# CubeSat_Power_Supply_Mk_3.net
KiCad netlist of a schematic drawn in EAGLE
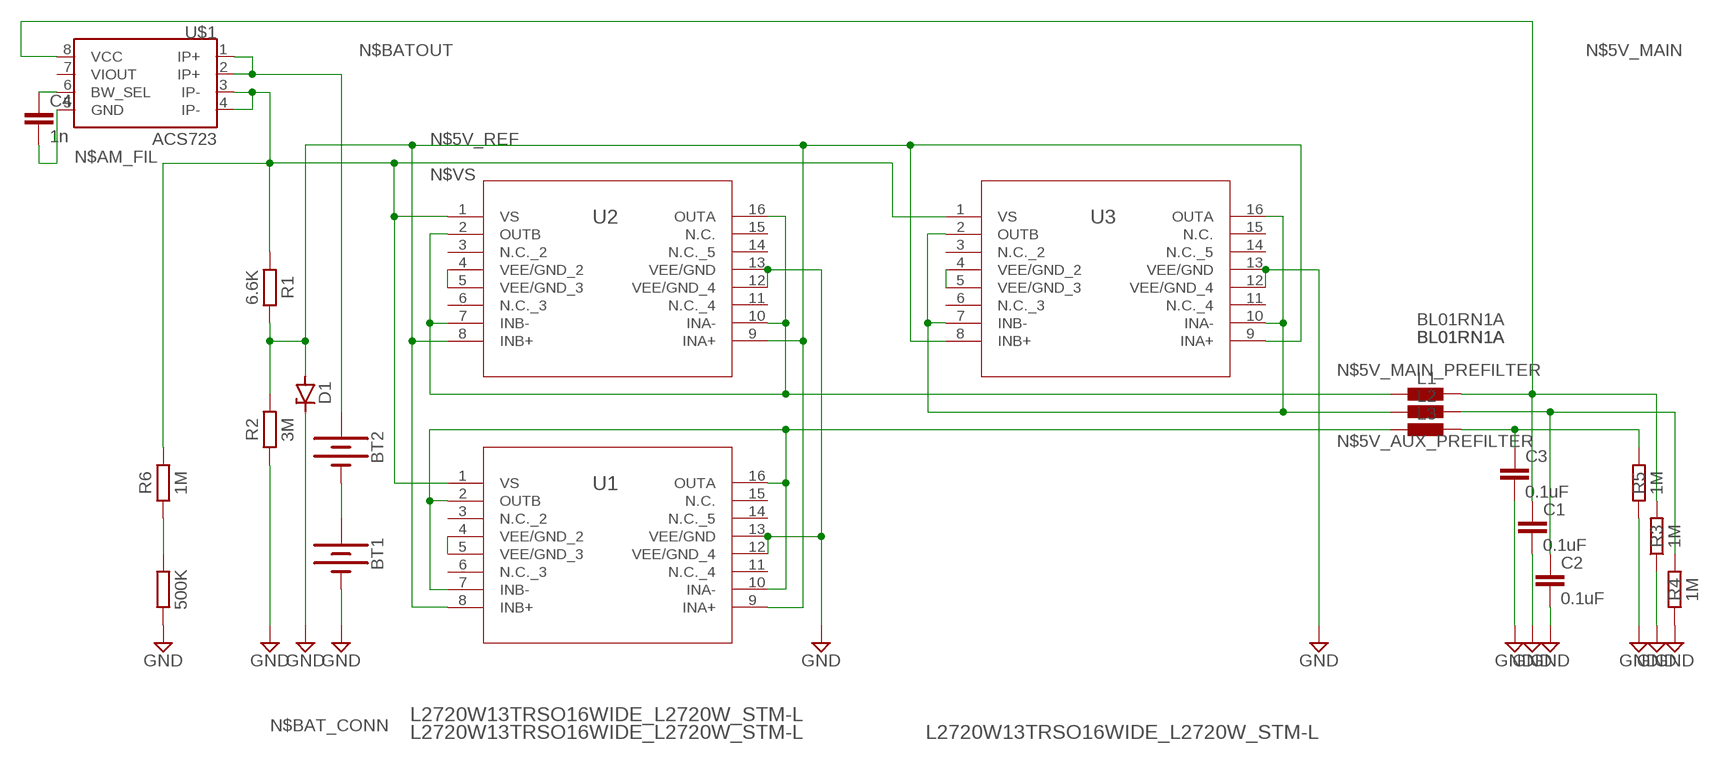
[diagram p0: schematic, sheet 1]

(export (version "E")
  (design (tool "Eeschema 10.0.6"))
  (components
    (comp (ref "BT1")
      (value "BATTERY-18650")
      (footprint "eagle-import:BATTERY_18650-HOLDER")
      (libsource (lib "eagle-import") (part "BATTERY-18650"))
    )
    (comp (ref "BT2")
      (value "BATTERY-18650")
      (footprint "eagle-import:BATTERY_18650-HOLDER")
      (libsource (lib "eagle-import") (part "BATTERY-18650"))
    )
    (comp (ref "C1")
      (value "0.1uF")
      (footprint "eagle-import:CAP-PTH-SMALL-KIT")
      (libsource (lib "eagle-import") (part "0.1UF-KIT-EZ-50V-20%"))
    )
    (comp (ref "C2")
      (value "0.1uF")
      (footprint "eagle-import:CAP-PTH-SMALL-KIT")
      (libsource (lib "eagle-import") (part "0.1UF-KIT-EZ-50V-20%"))
    )
    (comp (ref "C3")
      (value "0.1uF")
      (footprint "eagle-import:CAP-PTH-SMALL-KIT")
      (libsource (lib "eagle-import") (part "0.1UF-KIT-EZ-50V-20%"))
    )
    (comp (ref "C4")
      (value "1n")
      (footprint "eagle-import:CAP-PTH-SMALL-KIT")
      (libsource (lib "eagle-import") (part "0.1UF-KIT-EZ-50V-20%"))
    )
    (comp (ref "D1")
      (value "ZENER-DIODESOT23")
      (footprint "eagle-import:SOT23")
      (libsource (lib "eagle-import") (part "ZENER-DIODESOT23"))
    )
    (comp (ref "L1")
      (value "BL01RN1A")
      (footprint "eagle-import:BL01RN1A")
      (libsource (lib "eagle-import") (part "BL01RN1A"))
    )
    (comp (ref "L2")
      (value "BL01RN1A")
      (footprint "eagle-import:BL01RN1A")
      (libsource (lib "eagle-import") (part "BL01RN1A"))
    )
    (comp (ref "L3")
      (value "BL01RN1A")
      (footprint "eagle-import:BL01RN1A")
      (libsource (lib "eagle-import") (part "BL01RN1A"))
    )
    (comp (ref "R1")
      (value "6.6K")
      (footprint "eagle-import:RESAD724W46L381D178B")
      (libsource (lib "eagle-import") (part "RAXIAL-7.2MM-PITCH_"))
    )
    (comp (ref "R2")
      (value "3M")
      (footprint "eagle-import:RESAD724W46L381D178B")
      (libsource (lib "eagle-import") (part "RAXIAL-7.2MM-PITCH_"))
    )
    (comp (ref "R3")
      (value "1M")
      (footprint "eagle-import:RESAD724W46L381D178B")
      (libsource (lib "eagle-import") (part "RAXIAL-7.2MM-PITCH_"))
    )
    (comp (ref "R4")
      (value "1M")
      (footprint "eagle-import:RESAD724W46L381D178B")
      (libsource (lib "eagle-import") (part "RAXIAL-7.2MM-PITCH_"))
    )
    (comp (ref "R5")
      (value "1M")
      (footprint "eagle-import:RESAD724W46L381D178B")
      (libsource (lib "eagle-import") (part "RAXIAL-7.2MM-PITCH_"))
    )
    (comp (ref "R6")
      (value "1M")
      (footprint "eagle-import:RESAD724W46L381D178B")
      (libsource (lib "eagle-import") (part "RAXIAL-7.2MM-PITCH_"))
    )
    (comp (ref "R7")
      (value "500K")
      (footprint "eagle-import:RESAD724W46L381D178B")
      (libsource (lib "eagle-import") (part "RAXIAL-7.2MM-PITCH_"))
    )
    (comp (ref "U$1")
      (value "ACS723")
      (footprint "eagle-import:SO08")
      (fields (field (name "PART_#") "ACS723ACS723LLCTR-05AB-T2"))
      (libsource (lib "eagle-import") (part "ACS723"))
    )
    (comp (ref "U1")
      (value "L2720W13TRSO16WIDE_L2720W_STM-L")
      (footprint "eagle-import:SO16WIDE_L2720W_STM-L")
      (fields
        (field (name "MANUFACTURER_PART_NUMBER") "L2720W13TR")
        (field (name "COPYRIGHT") "Copyright (C) 2024 Ultra Librarian. All rights reserved.")
      )
      (libsource (lib "eagle-import") (part "L2720W13TRSO16WIDE_L2720W_STM-L"))
    )
    (comp (ref "U2")
      (value "L2720W13TRSO16WIDE_L2720W_STM-L")
      (footprint "eagle-import:SO16WIDE_L2720W_STM-L")
      (fields
        (field (name "MANUFACTURER_PART_NUMBER") "L2720W13TR")
        (field (name "COPYRIGHT") "Copyright (C) 2024 Ultra Librarian. All rights reserved.")
      )
      (libsource (lib "eagle-import") (part "L2720W13TRSO16WIDE_L2720W_STM-L"))
    )
    (comp (ref "U3")
      (value "L2720W13TRSO16WIDE_L2720W_STM-L")
      (footprint "eagle-import:SO16WIDE_L2720W_STM-L")
      (fields
        (field (name "MANUFACTURER_PART_NUMBER") "L2720W13TR")
        (field (name "COPYRIGHT") "Copyright (C) 2024 Ultra Librarian. All rights reserved.")
      )
      (libsource (lib "eagle-import") (part "L2720W13TRSO16WIDE_L2720W_STM-L"))
    )
  )
  (nets
    (net (code "1") (name "/N$5V_AUX_PREFILTER") (class "Default")
      (node (ref "L2") (pin "1") (pinfunction "1_1") (pintype "passive"))
      (node (ref "U3") (pin "10") (pinfunction "INA-_10") (pintype "input"))
      (node (ref "U3") (pin "16") (pinfunction "OUTA_16") (pintype "output"))
      (node (ref "U3") (pin "2") (pinfunction "OUTB_2") (pintype "output"))
      (node (ref "U3") (pin "7") (pinfunction "INB-_7") (pintype "input"))
    )
    (net (code "2") (name "/N$5V_MAIN") (class "Default")
      (node (ref "C1") (pin "1") (pinfunction "1_1") (pintype "passive"))
      (node (ref "L1") (pin "2") (pinfunction "2_2") (pintype "passive"))
      (node (ref "R3") (pin "2") (pinfunction "2_2") (pintype "passive"))
      (node (ref "U$1") (pin "8") (pinfunction "VCC_8") (pintype "bidirectional"))
    )
    (net (code "3") (name "/N$5V_MAIN_PREFILTER") (class "Default")
      (node (ref "L1") (pin "1") (pinfunction "1_1") (pintype "passive"))
      (node (ref "U2") (pin "10") (pinfunction "INA-_10") (pintype "input"))
      (node (ref "U2") (pin "16") (pinfunction "OUTA_16") (pintype "output"))
      (node (ref "U2") (pin "2") (pinfunction "OUTB_2") (pintype "output"))
      (node (ref "U2") (pin "7") (pinfunction "INB-_7") (pintype "input"))
    )
    (net (code "4") (name "/N$5V_REF") (class "Default")
      (node (ref "D1") (pin "1") (pinfunction "A_1") (pintype "passive"))
      (node (ref "R1") (pin "2") (pinfunction "2_2") (pintype "passive"))
      (node (ref "R2") (pin "2") (pinfunction "2_2") (pintype "passive"))
      (node (ref "U1") (pin "8") (pinfunction "INB+_8") (pintype "input"))
      (node (ref "U1") (pin "9") (pinfunction "INA+_9") (pintype "input"))
      (node (ref "U2") (pin "8") (pinfunction "INB+_8") (pintype "input"))
      (node (ref "U2") (pin "9") (pinfunction "INA+_9") (pintype "input"))
      (node (ref "U3") (pin "8") (pinfunction "INB+_8") (pintype "input"))
      (node (ref "U3") (pin "9") (pinfunction "INA+_9") (pintype "input"))
    )
    (net (code "5") (name "/N$AM_FIL") (class "Default")
      (node (ref "C4") (pin "1") (pinfunction "1_1") (pintype "passive"))
      (node (ref "U$1") (pin "6") (pinfunction "BW_SEL_6") (pintype "bidirectional"))
    )
    (net (code "6") (name "/N$BATOUT") (class "Default")
      (node (ref "BT2") (pin "PWR@1") (pinfunction "+_PWR@1") (pintype "power_in"))
      (node (ref "U$1") (pin "1") (pinfunction "IP+_1") (pintype "input"))
      (node (ref "U$1") (pin "2") (pinfunction "IP+_2") (pintype "input"))
    )
    (net (code "7") (name "/N$BAT_CONN") (class "Default")
      (node (ref "BT1") (pin "PWR@1") (pinfunction "+_PWR@1") (pintype "power_in"))
      (node (ref "BT2") (pin "GND@1") (pinfunction "-_GND@1") (pintype "power_in"))
    )
    (net (code "8") (name "/N$VS") (class "Default")
      (node (ref "R1") (pin "1") (pinfunction "1_1") (pintype "passive"))
      (node (ref "R6") (pin "2") (pinfunction "2_2") (pintype "passive"))
      (node (ref "U$1") (pin "3") (pinfunction "IP-_3") (pintype "bidirectional"))
      (node (ref "U$1") (pin "4") (pinfunction "IP-_4") (pintype "bidirectional"))
      (node (ref "U1") (pin "1") (pinfunction "VS_1") (pintype "power_in"))
      (node (ref "U2") (pin "1") (pinfunction "VS_1") (pintype "power_in"))
      (node (ref "U3") (pin "1") (pinfunction "VS_1") (pintype "power_in"))
    )
    (net (code "9") (name "GND") (class "Default")
      (node (ref "BT1") (pin "GND@1") (pinfunction "-_GND@1") (pintype "power_in"))
      (node (ref "C1") (pin "2") (pinfunction "2_2") (pintype "passive"))
      (node (ref "C2") (pin "2") (pinfunction "2_2") (pintype "passive"))
      (node (ref "C3") (pin "2") (pinfunction "2_2") (pintype "passive"))
      (node (ref "D1") (pin "3") (pinfunction "C_3") (pintype "passive"))
      (node (ref "R2") (pin "1") (pinfunction "1_1") (pintype "passive"))
      (node (ref "R3") (pin "1") (pinfunction "1_1") (pintype "passive"))
      (node (ref "R4") (pin "1") (pinfunction "1_1") (pintype "passive"))
      (node (ref "R5") (pin "1") (pinfunction "1_1") (pintype "passive"))
      (node (ref "R7") (pin "1") (pinfunction "1_1") (pintype "passive"))
      (node (ref "U1") (pin "12") (pinfunction "VEE/GND_4_12") (pintype "power_in"))
      (node (ref "U1") (pin "13") (pinfunction "VEE/GND_13") (pintype "power_in"))
      (node (ref "U2") (pin "12") (pinfunction "VEE/GND_4_12") (pintype "power_in"))
      (node (ref "U2") (pin "13") (pinfunction "VEE/GND_13") (pintype "power_in"))
      (node (ref "U3") (pin "12") (pinfunction "VEE/GND_4_12") (pintype "power_in"))
      (node (ref "U3") (pin "13") (pinfunction "VEE/GND_13") (pintype "power_in"))
    )
    (net (code "10") (name "Net-(C2-Pad1)") (class "Default")
      (node (ref "C2") (pin "1") (pinfunction "1_1") (pintype "passive"))
      (node (ref "L2") (pin "2") (pinfunction "2_2") (pintype "passive"))
      (node (ref "R4") (pin "2") (pinfunction "2_2") (pintype "passive"))
    )
    (net (code "11") (name "Net-(C3-Pad1)") (class "Default")
      (node (ref "C3") (pin "1") (pinfunction "1_1") (pintype "passive"))
      (node (ref "L3") (pin "2") (pinfunction "2_2") (pintype "passive"))
      (node (ref "R5") (pin "2") (pinfunction "2_2") (pintype "passive"))
    )
    (net (code "12") (name "Net-(R6-Pad1)") (class "Default")
      (node (ref "R6") (pin "1") (pinfunction "1_1") (pintype "passive"))
      (node (ref "R7") (pin "2") (pinfunction "2_2") (pintype "passive"))
    )
    (net (code "13") (name "Net-(U$1-GND)") (class "Default")
      (node (ref "C4") (pin "2") (pinfunction "2_2") (pintype "passive"))
      (node (ref "U$1") (pin "5") (pinfunction "GND_5") (pintype "bidirectional"))
    )
    (net (code "14") (name "Net-(U1-INA-)") (class "Default")
      (node (ref "L3") (pin "1") (pinfunction "1_1") (pintype "passive"))
      (node (ref "U1") (pin "10") (pinfunction "INA-_10") (pintype "input"))
      (node (ref "U1") (pin "16") (pinfunction "OUTA_16") (pintype "output"))
      (node (ref "U1") (pin "2") (pinfunction "OUTB_2") (pintype "output"))
      (node (ref "U1") (pin "7") (pinfunction "INB-_7") (pintype "input"))
    )
    (net (code "15") (name "Net-(U1-VEE{slash}GND_2)") (class "Default")
      (node (ref "U1") (pin "4") (pinfunction "VEE/GND_2_4") (pintype "power_in"))
      (node (ref "U1") (pin "5") (pinfunction "VEE/GND_3_5") (pintype "power_in"))
    )
    (net (code "16") (name "Net-(U2-VEE{slash}GND_2)") (class "Default")
      (node (ref "U2") (pin "4") (pinfunction "VEE/GND_2_4") (pintype "power_in"))
      (node (ref "U2") (pin "5") (pinfunction "VEE/GND_3_5") (pintype "power_in"))
    )
    (net (code "17") (name "Net-(U3-VEE{slash}GND_2)") (class "Default")
      (node (ref "U3") (pin "4") (pinfunction "VEE/GND_2_4") (pintype "power_in"))
      (node (ref "U3") (pin "5") (pinfunction "VEE/GND_3_5") (pintype "power_in"))
    )
    (net (code "18") (name "unconnected-(U$1-VIOUT-Pad7)") (class "Default")
      (node (ref "U$1") (pin "7") (pinfunction "VIOUT_7") (pintype "bidirectional"))
    )
    (net (code "19") (name "unconnected-(U1-N.C.-Pad15)") (class "Default")
      (node (ref "U1") (pin "15") (pinfunction "N.C._15") (pintype "no_connect"))
    )
    (net (code "20") (name "unconnected-(U1-N.C._2-Pad3)") (class "Default")
      (node (ref "U1") (pin "3") (pinfunction "N.C._2_3") (pintype "no_connect"))
    )
    (net (code "21") (name "unconnected-(U1-N.C._3-Pad6)") (class "Default")
      (node (ref "U1") (pin "6") (pinfunction "N.C._3_6") (pintype "no_connect"))
    )
    (net (code "22") (name "unconnected-(U1-N.C._4-Pad11)") (class "Default")
      (node (ref "U1") (pin "11") (pinfunction "N.C._4_11") (pintype "no_connect"))
    )
    (net (code "23") (name "unconnected-(U1-N.C._5-Pad14)") (class "Default")
      (node (ref "U1") (pin "14") (pinfunction "N.C._5_14") (pintype "no_connect"))
    )
    (net (code "24") (name "unconnected-(U2-N.C.-Pad15)") (class "Default")
      (node (ref "U2") (pin "15") (pinfunction "N.C._15") (pintype "no_connect"))
    )
    (net (code "25") (name "unconnected-(U2-N.C._2-Pad3)") (class "Default")
      (node (ref "U2") (pin "3") (pinfunction "N.C._2_3") (pintype "no_connect"))
    )
    (net (code "26") (name "unconnected-(U2-N.C._3-Pad6)") (class "Default")
      (node (ref "U2") (pin "6") (pinfunction "N.C._3_6") (pintype "no_connect"))
    )
    (net (code "27") (name "unconnected-(U2-N.C._4-Pad11)") (class "Default")
      (node (ref "U2") (pin "11") (pinfunction "N.C._4_11") (pintype "no_connect"))
    )
    (net (code "28") (name "unconnected-(U2-N.C._5-Pad14)") (class "Default")
      (node (ref "U2") (pin "14") (pinfunction "N.C._5_14") (pintype "no_connect"))
    )
    (net (code "29") (name "unconnected-(U3-N.C.-Pad15)") (class "Default")
      (node (ref "U3") (pin "15") (pinfunction "N.C._15") (pintype "no_connect"))
    )
    (net (code "30") (name "unconnected-(U3-N.C._2-Pad3)") (class "Default")
      (node (ref "U3") (pin "3") (pinfunction "N.C._2_3") (pintype "no_connect"))
    )
    (net (code "31") (name "unconnected-(U3-N.C._3-Pad6)") (class "Default")
      (node (ref "U3") (pin "6") (pinfunction "N.C._3_6") (pintype "no_connect"))
    )
    (net (code "32") (name "unconnected-(U3-N.C._4-Pad11)") (class "Default")
      (node (ref "U3") (pin "11") (pinfunction "N.C._4_11") (pintype "no_connect"))
    )
    (net (code "33") (name "unconnected-(U3-N.C._5-Pad14)") (class "Default")
      (node (ref "U3") (pin "14") (pinfunction "N.C._5_14") (pintype "no_connect"))
    )
  )
)
